# Sheet1.net
KiCad netlist of a schematic drawn in Altium Designer
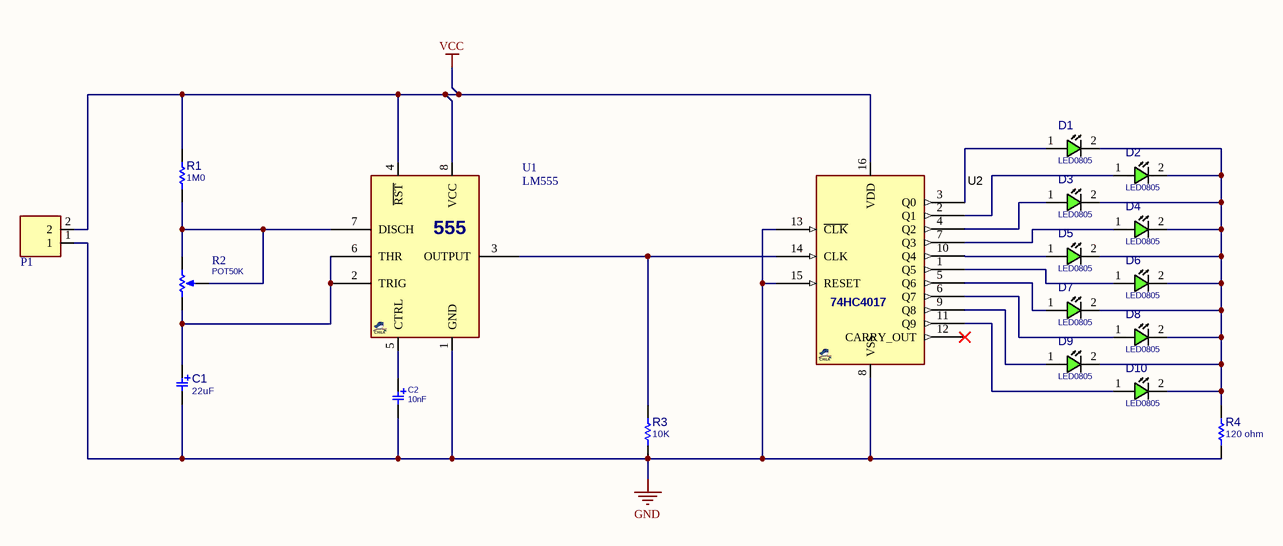
[diagram p0: Sheet1.SchDoc]

(export (version "E")
  (design (tool "Eeschema 10.0.6"))
  (components
    (comp (ref "C1")
      (value "22uF")
      (footprint "C_EL_D5L5")
      (description "CAP, SMD, ELEC,")
      (fields (field (name "MANF_P#") "MANF_PART#") (field (name "MANF") "MANF"))
      (libsource (lib "passive_smd") (part "CAP_SMD_EL"))
    )
    (comp (ref "C2")
      (value "10nF")
      (footprint "C_TN_3528")
      (description "CAP, SMD, TAN")
      (fields (field (name "MANF") "VISHAY") (field (name "MANF_P#") "T55A106M6R3C0300"))
      (libsource (lib "passive_smd") (part "CAP_SMD_TAN"))
    )
    (comp (ref "D1")
      (value "LED0805")
      (footprint "LED0805")
      (description "LED, SMD, 0805")
      (fields (field (name "MANF") "MANF") (field (name "MANF_P#") "MANF_PART#"))
      (libsource (lib "led(diode)") (part "LED_SMD_0805"))
    )
    (comp (ref "D2")
      (value "LED0805")
      (footprint "LED0805")
      (description "LED, SMD, 0805")
      (fields (field (name "MANF") "MANF") (field (name "MANF_P#") "MANF_PART#"))
      (libsource (lib "led(diode)") (part "LED_SMD_0805"))
    )
    (comp (ref "D3")
      (value "LED0805")
      (footprint "LED0805")
      (description "LED, SMD, 0805")
      (fields (field (name "MANF") "MANF") (field (name "MANF_P#") "MANF_PART#"))
      (libsource (lib "led(diode)") (part "LED_SMD_0805"))
    )
    (comp (ref "D4")
      (value "LED0805")
      (footprint "LED0805")
      (description "LED, SMD, 0805")
      (fields (field (name "MANF") "MANF") (field (name "MANF_P#") "MANF_PART#"))
      (libsource (lib "led(diode)") (part "LED_SMD_0805"))
    )
    (comp (ref "D5")
      (value "LED0805")
      (footprint "LED0805")
      (description "LED, SMD, 0805")
      (fields (field (name "MANF") "MANF") (field (name "MANF_P#") "MANF_PART#"))
      (libsource (lib "led(diode)") (part "LED_SMD_0805"))
    )
    (comp (ref "D6")
      (value "LED0805")
      (footprint "LED0805")
      (description "LED, SMD, 0805")
      (fields (field (name "MANF") "MANF") (field (name "MANF_P#") "MANF_PART#"))
      (libsource (lib "led(diode)") (part "LED_SMD_0805"))
    )
    (comp (ref "D7")
      (value "LED0805")
      (footprint "LED0805")
      (description "LED, SMD, 0805")
      (fields (field (name "MANF") "MANF") (field (name "MANF_P#") "MANF_PART#"))
      (libsource (lib "led(diode)") (part "LED_SMD_0805"))
    )
    (comp (ref "D8")
      (value "LED0805")
      (footprint "LED0805")
      (description "LED, SMD, 0805")
      (fields (field (name "MANF") "MANF") (field (name "MANF_P#") "MANF_PART#"))
      (libsource (lib "led(diode)") (part "LED_SMD_0805"))
    )
    (comp (ref "D9")
      (value "LED0805")
      (footprint "LED0805")
      (description "LED, SMD, 0805")
      (fields (field (name "MANF") "MANF") (field (name "MANF_P#") "MANF_PART#"))
      (libsource (lib "led(diode)") (part "LED_SMD_0805"))
    )
    (comp (ref "D10")
      (value "LED0805")
      (footprint "LED0805")
      (description "LED, SMD, 0805")
      (fields (field (name "MANF") "MANF") (field (name "MANF_P#") "MANF_PART#"))
      (libsource (lib "led(diode)") (part "LED_SMD_0805"))
    )
    (comp (ref "P1")
      (value "CONN_PWL_2")
      (footprint "PWL_2")
      (description "Power Terminal 2pin,Header, 2-Pin")
      (libsource (lib "conn_power") (part "CONN_PWL_2"))
    )
    (comp (ref "R1")
      (value "1M0")
      (footprint "R0805")
      (description "RESISTOR, SMD")
      (libsource (lib "passive_smd") (part "RES_SMD_0805"))
    )
    (comp (ref "R2")
      (value "POT50K")
      (footprint "POTS_V10MM")
      (description "RESISTOR, SMD, Potentiometer, 10mm")
      (libsource (lib "resistor_pot_trimmer") (part "RES_SMD_POT_V10"))
    )
    (comp (ref "R3")
      (value "10K")
      (footprint "R0805")
      (description "RESISTOR, SMD")
      (libsource (lib "passive_smd") (part "RES_SMD_0805"))
    )
    (comp (ref "R4")
      (value "120 ohm")
      (footprint "R0805")
      (description "RESISTOR, SMD")
      (libsource (lib "passive_smd") (part "RES_SMD_0805"))
    )
    (comp (ref "U1")
      (value "LM555")
      (footprint "SO_8")
      (description "555 Timer,")
      (fields (field (name "MANF") "Texas Instruments") (field (name "MANF_P#") "LM555CMX, LMC555CM"))
      (libsource (lib "ic_timer_555") (part "LM555C_SOP8"))
    )
    (comp (ref "U2")
      (value "74HC4017")
      (footprint "SO_16")
      (description "Counter, 10 decoded output")
      (fields (field (name "MANF") "NXP, TI") (field (name "MANF_P#") "74HC4017D, CD74HC4017M"))
      (libsource (lib "logic_counter") (part "74HC4017_SOP16"))
    )
  )
  (nets
    (net (code "1") (name "GND") (class "Default")
      (node (ref "C1") (pin "2") (pinfunction "2_2") (pintype "passive"))
      (node (ref "C2") (pin "2") (pinfunction "2_2") (pintype "passive"))
      (node (ref "P1") (pin "1") (pinfunction "1_1") (pintype "passive"))
      (node (ref "R3") (pin "1") (pinfunction "1_1") (pintype "passive"))
      (node (ref "R4") (pin "1") (pinfunction "1_1") (pintype "passive"))
      (node (ref "U1") (pin "1") (pinfunction "GND_1") (pintype "passive"))
      (node (ref "U2") (pin "13") (pinfunction "~{CLK}_13") (pintype "input"))
      (node (ref "U2") (pin "15") (pinfunction "RESET_15") (pintype "input"))
      (node (ref "U2") (pin "8") (pinfunction "VSS_8") (pintype "power_in"))
    )
    (net (code "2") (name "Net-(D1-ANODE)") (class "Default")
      (node (ref "D1") (pin "1") (pinfunction "ANODE_1") (pintype "passive"))
      (node (ref "U2") (pin "3") (pinfunction "Q0_3") (pintype "output"))
    )
    (net (code "3") (name "Net-(D1-CATHODE)") (class "Default")
      (node (ref "D1") (pin "2") (pinfunction "CATHODE_2") (pintype "passive"))
      (node (ref "D10") (pin "2") (pinfunction "CATHODE_2") (pintype "passive"))
      (node (ref "D2") (pin "2") (pinfunction "CATHODE_2") (pintype "passive"))
      (node (ref "D3") (pin "2") (pinfunction "CATHODE_2") (pintype "passive"))
      (node (ref "D4") (pin "2") (pinfunction "CATHODE_2") (pintype "passive"))
      (node (ref "D5") (pin "2") (pinfunction "CATHODE_2") (pintype "passive"))
      (node (ref "D6") (pin "2") (pinfunction "CATHODE_2") (pintype "passive"))
      (node (ref "D7") (pin "2") (pinfunction "CATHODE_2") (pintype "passive"))
      (node (ref "D8") (pin "2") (pinfunction "CATHODE_2") (pintype "passive"))
      (node (ref "D9") (pin "2") (pinfunction "CATHODE_2") (pintype "passive"))
      (node (ref "R4") (pin "2") (pinfunction "2_2") (pintype "passive"))
    )
    (net (code "4") (name "Net-(D2-ANODE)") (class "Default")
      (node (ref "D2") (pin "1") (pinfunction "ANODE_1") (pintype "passive"))
      (node (ref "U2") (pin "2") (pinfunction "Q1_2") (pintype "output"))
    )
    (net (code "5") (name "Net-(D3-ANODE)") (class "Default")
      (node (ref "D3") (pin "1") (pinfunction "ANODE_1") (pintype "passive"))
      (node (ref "U2") (pin "4") (pinfunction "Q2_4") (pintype "output"))
    )
    (net (code "6") (name "Net-(D4-ANODE)") (class "Default")
      (node (ref "D4") (pin "1") (pinfunction "ANODE_1") (pintype "passive"))
      (node (ref "U2") (pin "7") (pinfunction "Q3_7") (pintype "output"))
    )
    (net (code "7") (name "Net-(D5-ANODE)") (class "Default")
      (node (ref "D5") (pin "1") (pinfunction "ANODE_1") (pintype "passive"))
      (node (ref "U2") (pin "10") (pinfunction "Q4_10") (pintype "output"))
    )
    (net (code "8") (name "Net-(D6-ANODE)") (class "Default")
      (node (ref "D6") (pin "1") (pinfunction "ANODE_1") (pintype "passive"))
      (node (ref "U2") (pin "1") (pinfunction "Q5_1") (pintype "output"))
    )
    (net (code "9") (name "Net-(D7-ANODE)") (class "Default")
      (node (ref "D7") (pin "1") (pinfunction "ANODE_1") (pintype "passive"))
      (node (ref "U2") (pin "5") (pinfunction "Q6_5") (pintype "output"))
    )
    (net (code "10") (name "Net-(D8-ANODE)") (class "Default")
      (node (ref "D8") (pin "1") (pinfunction "ANODE_1") (pintype "passive"))
      (node (ref "U2") (pin "6") (pinfunction "Q7_6") (pintype "output"))
    )
    (net (code "11") (name "Net-(D9-ANODE)") (class "Default")
      (node (ref "D9") (pin "1") (pinfunction "ANODE_1") (pintype "passive"))
      (node (ref "U2") (pin "9") (pinfunction "Q8_9") (pintype "output"))
    )
    (net (code "12") (name "Net-(D10-ANODE)") (class "Default")
      (node (ref "D10") (pin "1") (pinfunction "ANODE_1") (pintype "passive"))
      (node (ref "U2") (pin "11") (pinfunction "Q9_11") (pintype "output"))
    )
    (net (code "13") (name "Net-(R2-BOT)") (class "Default")
      (node (ref "R1") (pin "1") (pinfunction "1_1") (pintype "passive"))
      (node (ref "R2") (pin "2") (pinfunction "TAP_2") (pintype "passive"))
      (node (ref "R2") (pin "3") (pinfunction "BOT_3") (pintype "passive"))
      (node (ref "U1") (pin "7") (pinfunction "DISCH_7") (pintype "passive"))
    )
    (net (code "14") (name "Net-(R2-TOP)") (class "Default")
      (node (ref "C1") (pin "1") (pinfunction "1_1") (pintype "passive"))
      (node (ref "R2") (pin "1") (pinfunction "TOP_1") (pintype "passive"))
      (node (ref "U1") (pin "2") (pinfunction "TRIG_2") (pintype "passive"))
      (node (ref "U1") (pin "6") (pinfunction "THR_6") (pintype "passive"))
    )
    (net (code "15") (name "Net-(U1-CTRL)") (class "Default")
      (node (ref "C2") (pin "1") (pinfunction "1_1") (pintype "passive"))
      (node (ref "U1") (pin "5") (pinfunction "CTRL_5") (pintype "passive"))
    )
    (net (code "16") (name "Net-(U1-OUTPUT)") (class "Default")
      (node (ref "R3") (pin "2") (pinfunction "2_2") (pintype "passive"))
      (node (ref "U1") (pin "3") (pinfunction "OUTPUT_3") (pintype "passive"))
      (node (ref "U2") (pin "14") (pinfunction "CLK_14") (pintype "input"))
    )
    (net (code "17") (name "VCC") (class "Default")
      (node (ref "P1") (pin "2") (pinfunction "2_2") (pintype "passive"))
      (node (ref "R1") (pin "2") (pinfunction "2_2") (pintype "passive"))
      (node (ref "U1") (pin "4") (pinfunction "~{RST}_4") (pintype "passive"))
      (node (ref "U1") (pin "8") (pinfunction "VCC_8") (pintype "passive"))
      (node (ref "U2") (pin "16") (pinfunction "VDD_16") (pintype "power_in"))
    )
    (net (code "18") (name "unconnected-(U2-CARRY_OUT-Pad12)") (class "Default")
      (node (ref "U2") (pin "12") (pinfunction "CARRY_OUT_12") (pintype "output+no_connect"))
    )
  )
)
